# Sensor_Module_0x06_CO2_CCS811_v2.net
KiCad netlist of a schematic drawn in EAGLE
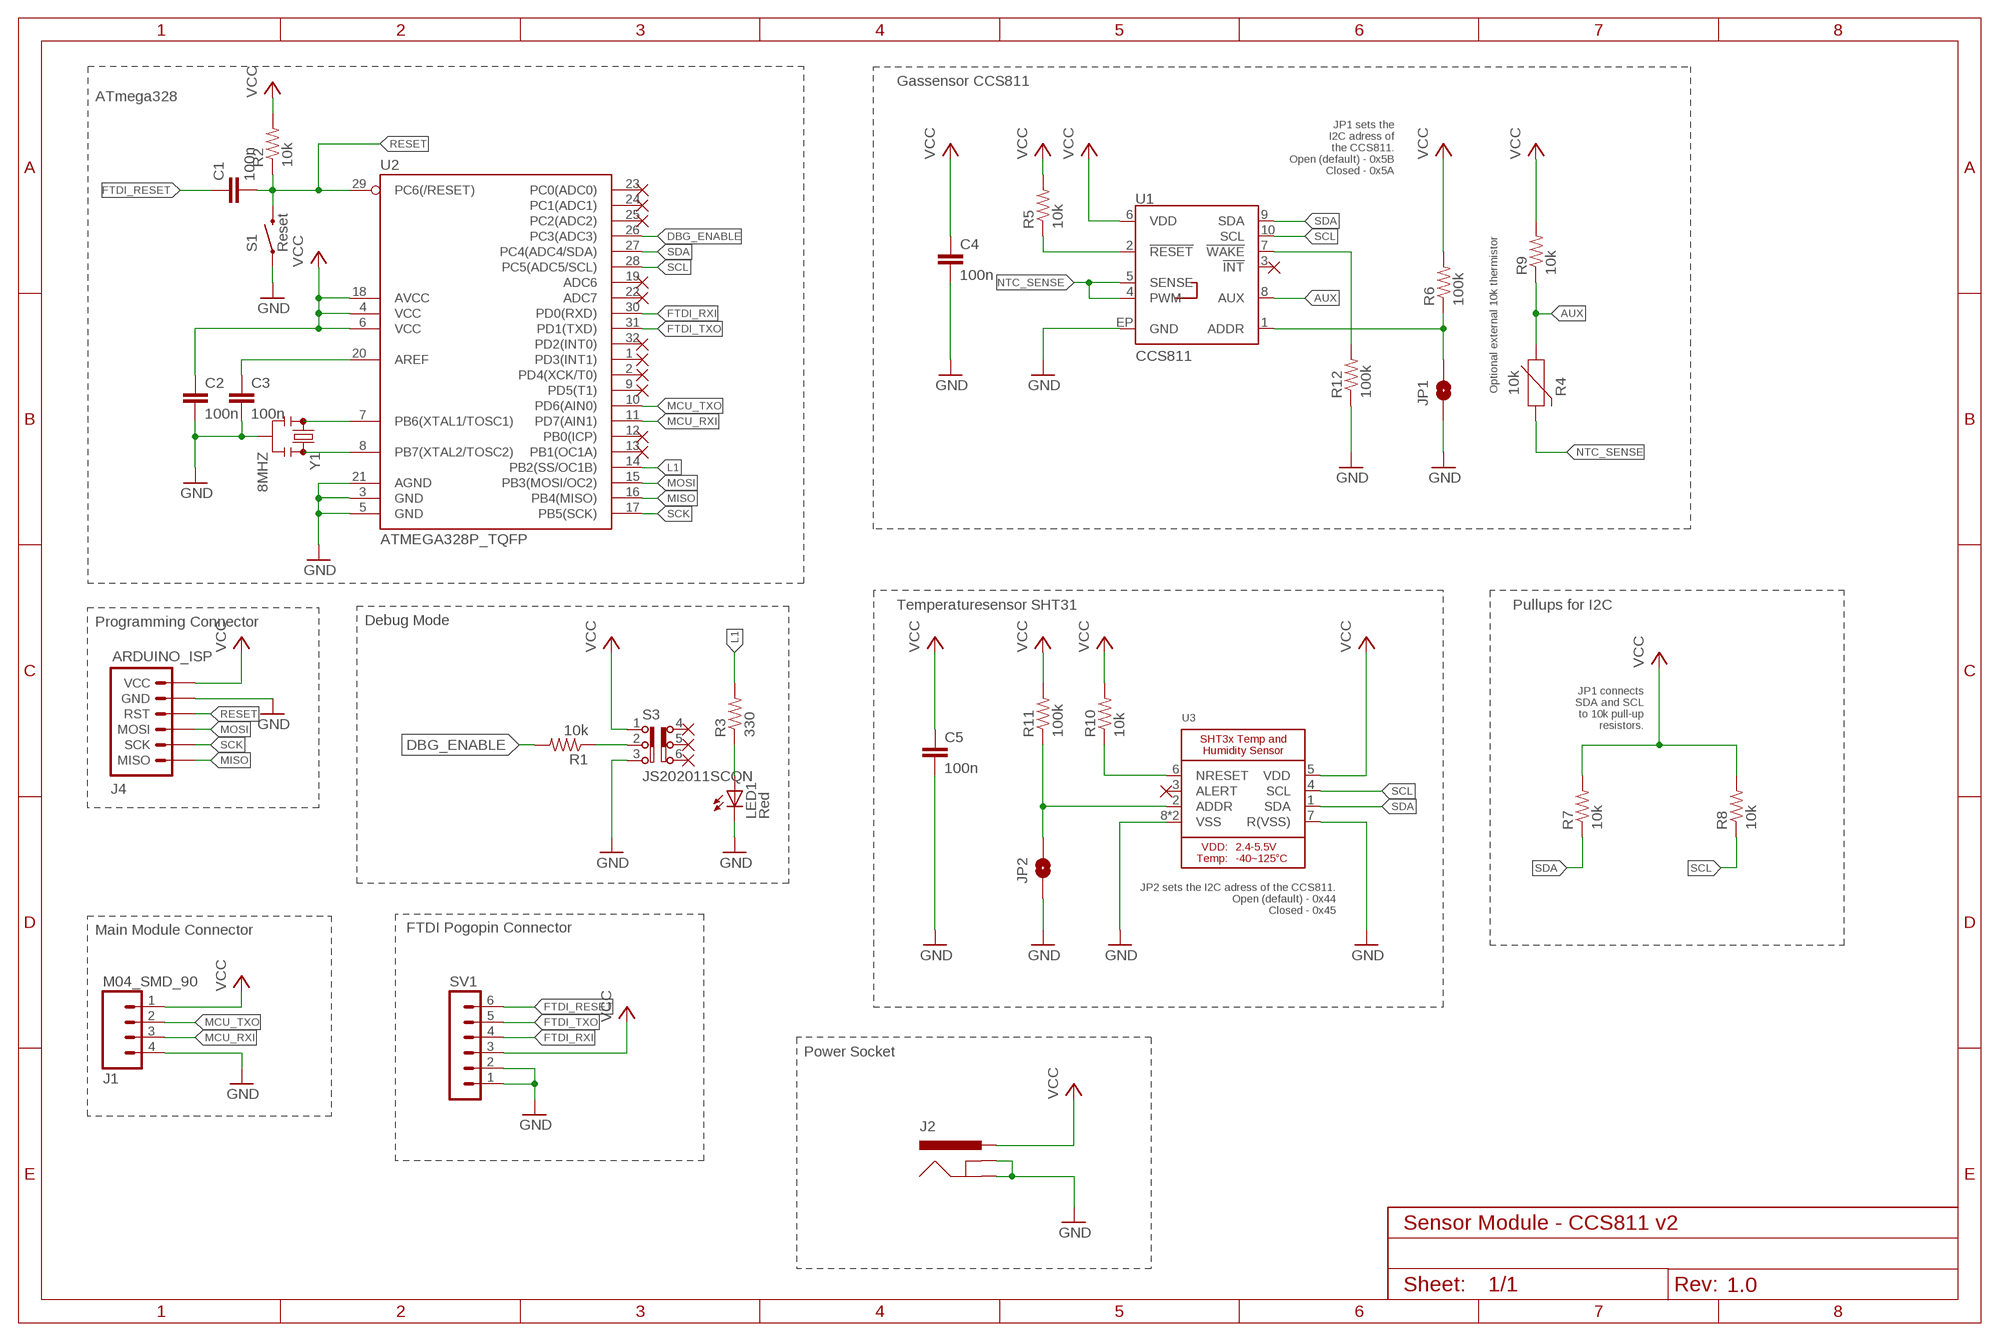
[diagram p0: schematic, sheet 1]

(export (version "E")
  (design (tool "Eeschema 10.0.6"))
  (components
    (comp (ref "C1")
      (value "100n")
      (footprint "eagle-import:C0805")
      (libsource (lib "eagle-import") (part "C"))
    )
    (comp (ref "C2")
      (value "100n")
      (footprint "eagle-import:C0805")
      (libsource (lib "eagle-import") (part "C"))
    )
    (comp (ref "C3")
      (value "100n")
      (footprint "eagle-import:C0805")
      (libsource (lib "eagle-import") (part "C"))
    )
    (comp (ref "C4")
      (value "100n")
      (footprint "eagle-import:C0805")
      (libsource (lib "eagle-import") (part "C"))
    )
    (comp (ref "C5")
      (value "100n")
      (footprint "eagle-import:C0805")
      (libsource (lib "eagle-import") (part "C"))
    )
    (comp (ref "J1")
      (value "M04_SMD_90")
      (footprint "eagle-import:M04_SMD_90")
      (libsource (lib "eagle-import") (part "M04_SMD_90"))
    )
    (comp (ref "J2")
      (value "5.5x2.1mm Barrel")
      (footprint "eagle-import:POWER_JACK_SMD")
      (libsource (lib "eagle-import") (part "POWER_JACKSMD"))
    )
    (comp (ref "J4")
      (value "ARDUINO_ISP")
      (footprint "eagle-import:M-2X3")
      (libsource (lib "eagle-import") (part "ARDUINO_ISP"))
    )
    (comp (ref "JP1")
      (value "SPARKFUN-JUMPERS_JUMPER-SMT_2_NO_SILK")
      (footprint "eagle-import:SPARKFUN-JUMPERS_SMT-JUMPER_2_NO_SILK")
      (libsource (lib "eagle-import") (part "SPARKFUN-JUMPERS_JUMPER-SMT_2_NO_SILK"))
    )
    (comp (ref "JP2")
      (value "SPARKFUN-JUMPERS_JUMPER-SMT_2_NO_SILK")
      (footprint "eagle-import:SPARKFUN-JUMPERS_SMT-JUMPER_2_NO_SILK")
      (libsource (lib "eagle-import") (part "SPARKFUN-JUMPERS_JUMPER-SMT_2_NO_SILK"))
    )
    (comp (ref "LED1")
      (value "Red")
      (footprint "eagle-import:SML0805")
      (libsource (lib "eagle-import") (part "LEDSML0805"))
    )
    (comp (ref "R1")
      (value "10k")
      (footprint "eagle-import:0805")
      (libsource (lib "eagle-import") (part "RESISTOR0805-RES"))
    )
    (comp (ref "R2")
      (value "10k")
      (footprint "eagle-import:0805")
      (libsource (lib "eagle-import") (part "RESISTOR0805-RES"))
    )
    (comp (ref "R3")
      (value "330")
      (footprint "eagle-import:0805")
      (libsource (lib "eagle-import") (part "RESISTOR0805-RES"))
    )
    (comp (ref "R4")
      (value "10k")
      (footprint "eagle-import:CCS811_BREAKOUT_TEMP_0603")
      (libsource (lib "eagle-import") (part "CCS811_BREAKOUT_TEMP_NTC-THERMISTOR-0603"))
    )
    (comp (ref "R5")
      (value "10k")
      (footprint "eagle-import:0805")
      (libsource (lib "eagle-import") (part "RESISTOR0805-RES"))
    )
    (comp (ref "R6")
      (value "100k")
      (footprint "eagle-import:0805")
      (libsource (lib "eagle-import") (part "RESISTOR0805-RES"))
    )
    (comp (ref "R7")
      (value "10k")
      (footprint "eagle-import:0805")
      (libsource (lib "eagle-import") (part "RESISTOR0805-RES"))
    )
    (comp (ref "R8")
      (value "10k")
      (footprint "eagle-import:0805")
      (libsource (lib "eagle-import") (part "RESISTOR0805-RES"))
    )
    (comp (ref "R9")
      (value "10k")
      (footprint "eagle-import:0805")
      (libsource (lib "eagle-import") (part "RESISTOR0805-RES"))
    )
    (comp (ref "R10")
      (value "10k")
      (footprint "eagle-import:0805")
      (libsource (lib "eagle-import") (part "RESISTOR0805-RES"))
    )
    (comp (ref "R11")
      (value "100k")
      (footprint "eagle-import:0805")
      (libsource (lib "eagle-import") (part "RESISTOR0805-RES"))
    )
    (comp (ref "R12")
      (value "100k")
      (footprint "eagle-import:0805")
      (libsource (lib "eagle-import") (part "RESISTOR0805-RES"))
    )
    (comp (ref "S1")
      (value "Reset")
      (footprint "eagle-import:M-PUSHBUTTON-SMD")
      (libsource (lib "eagle-import") (part "PUSHBUTTON"))
    )
    (comp (ref "S3")
      (value "JS202011SCQN")
      (footprint "eagle-import:JS202011SCQN")
      (libsource (lib "eagle-import") (part "JS202011SCQN"))
    )
    (comp (ref "SV1")
      (value "MA06-1")
      (footprint "eagle-import:MA06-1")
      (libsource (lib "eagle-import") (part "MA06-1"))
    )
    (comp (ref "U1")
      (value "CCS811")
      (footprint "eagle-import:CCS811_BREAKOUT_TEMP_LGA10")
      (libsource (lib "eagle-import") (part "CCS811_BREAKOUT_TEMP_CCS811"))
    )
    (comp (ref "U2")
      (value "ATMEGA328P_TQFP")
      (footprint "eagle-import:TQFP32-08")
      (libsource (lib "eagle-import") (part "ATMEGA328P_TQFP"))
    )
    (comp (ref "U3")
      (value "MICROBUILDER_SHT3X")
      (footprint "eagle-import:MICROBUILDER_SHT3X")
      (libsource (lib "eagle-import") (part "MICROBUILDER_SHT3X"))
    )
    (comp (ref "Y1")
      (value "8MHZ")
      (footprint "eagle-import:RESONATOR-SMD")
      (libsource (lib "eagle-import") (part "RESONATOR8MHZ"))
    )
  )
  (nets
    (net (code "1") (name "AUX") (class "Default")
      (node (ref "R4") (pin "1") (pinfunction "1_1") (pintype "bidirectional"))
      (node (ref "R9") (pin "1") (pinfunction "1_1") (pintype "passive"))
      (node (ref "U1") (pin "8") (pinfunction "AUX_8") (pintype "bidirectional"))
    )
    (net (code "2") (name "DBG_ENABLE") (class "Default")
      (node (ref "R1") (pin "2") (pinfunction "2_2") (pintype "passive"))
      (node (ref "U2") (pin "26") (pinfunction "PC3(ADC3)_26") (pintype "bidirectional"))
    )
    (net (code "3") (name "FTDI_RESET") (class "Default")
      (node (ref "C1") (pin "1") (pinfunction "1_1") (pintype "passive"))
      (node (ref "SV1") (pin "6") (pinfunction "6_6") (pintype "passive"))
    )
    (net (code "4") (name "FTDI_RXI") (class "Default")
      (node (ref "SV1") (pin "4") (pinfunction "4_4") (pintype "passive"))
      (node (ref "U2") (pin "30") (pinfunction "PD0(RXD)_30") (pintype "bidirectional"))
    )
    (net (code "5") (name "FTDI_TXO") (class "Default")
      (node (ref "SV1") (pin "5") (pinfunction "5_5") (pintype "passive"))
      (node (ref "U2") (pin "31") (pinfunction "PD1(TXD)_31") (pintype "bidirectional"))
    )
    (net (code "6") (name "GND") (class "Default")
      (node (ref "C2") (pin "2") (pinfunction "2_2") (pintype "passive"))
      (node (ref "C3") (pin "2") (pinfunction "2_2") (pintype "passive"))
      (node (ref "C4") (pin "2") (pinfunction "2_2") (pintype "passive"))
      (node (ref "C5") (pin "2") (pinfunction "2_2") (pintype "passive"))
      (node (ref "J1") (pin "4") (pinfunction "4_4") (pintype "passive"))
      (node (ref "J2") (pin "GND") (pinfunction "GNDBREAK_GND") (pintype "bidirectional"))
      (node (ref "J2") (pin "P$4") (pinfunction "GND_P$4") (pintype "bidirectional"))
      (node (ref "J4") (pin "P$5") (pinfunction "GND_P$5") (pintype "passive"))
      (node (ref "JP1") (pin "1") (pinfunction "1_1") (pintype "passive"))
      (node (ref "JP2") (pin "1") (pinfunction "1_1") (pintype "passive"))
      (node (ref "LED1") (pin "C") (pinfunction "C_C") (pintype "passive"))
      (node (ref "R12") (pin "1") (pinfunction "1_1") (pintype "passive"))
      (node (ref "S1") (pin "1") (pinfunction "LEFT_1") (pintype "passive"))
      (node (ref "S1") (pin "2") (pinfunction "LEFT_2") (pintype "passive"))
      (node (ref "S3") (pin "3") (pinfunction "3_3") (pintype "passive"))
      (node (ref "SV1") (pin "1") (pinfunction "1_1") (pintype "passive"))
      (node (ref "SV1") (pin "2") (pinfunction "2_2") (pintype "passive"))
      (node (ref "U1") (pin "EP") (pinfunction "GND_EP") (pintype "bidirectional"))
      (node (ref "U2") (pin "21") (pinfunction "AGND_21") (pintype "bidirectional"))
      (node (ref "U2") (pin "3") (pinfunction "GND_3") (pintype "bidirectional"))
      (node (ref "U2") (pin "5") (pinfunction "GND_5") (pintype "bidirectional"))
      (node (ref "U3") (pin "7") (pinfunction "R(VSS)_7") (pintype "bidirectional"))
      (node (ref "U3") (pin "8") (pinfunction "VSS_8") (pintype "power_in"))
      (node (ref "U3") (pin "THERMAL") (pinfunction "VSS_THERMAL") (pintype "power_in"))
      (node (ref "Y1") (pin "2") (pinfunction "2_2") (pintype "passive"))
    )
    (net (code "7") (name "L1") (class "Default")
      (node (ref "R3") (pin "2") (pinfunction "2_2") (pintype "passive"))
      (node (ref "U2") (pin "14") (pinfunction "PB2(SS/OC1B)_14") (pintype "bidirectional"))
    )
    (net (code "8") (name "MCU_RXI") (class "Default")
      (node (ref "J1") (pin "3") (pinfunction "3_3") (pintype "passive"))
      (node (ref "U2") (pin "11") (pinfunction "PD7(AIN1)_11") (pintype "bidirectional"))
    )
    (net (code "9") (name "MCU_TXO") (class "Default")
      (node (ref "J1") (pin "2") (pinfunction "2_2") (pintype "passive"))
      (node (ref "U2") (pin "10") (pinfunction "PD6(AIN0)_10") (pintype "bidirectional"))
    )
    (net (code "10") (name "MISO") (class "Default")
      (node (ref "J4") (pin "P$1") (pinfunction "MISO_P$1") (pintype "passive"))
      (node (ref "U2") (pin "16") (pinfunction "PB4(MISO)_16") (pintype "bidirectional"))
    )
    (net (code "11") (name "MOSI") (class "Default")
      (node (ref "J4") (pin "P$3") (pinfunction "MOSI_P$3") (pintype "passive"))
      (node (ref "U2") (pin "15") (pinfunction "PB3(MOSI/OC2)_15") (pintype "bidirectional"))
    )
    (net (code "12") (name "NTC_SENSE") (class "Default")
      (node (ref "R4") (pin "2") (pinfunction "2_2") (pintype "bidirectional"))
      (node (ref "U1") (pin "4") (pinfunction "PWM_4") (pintype "bidirectional"))
      (node (ref "U1") (pin "5") (pinfunction "SENSE_5") (pintype "bidirectional"))
    )
    (net (code "13") (name "Net-(LED1-PadA)") (class "Default")
      (node (ref "LED1") (pin "A") (pinfunction "A_A") (pintype "passive"))
      (node (ref "R3") (pin "1") (pinfunction "1_1") (pintype "passive"))
    )
    (net (code "14") (name "Net-(R1-Pad1)") (class "Default")
      (node (ref "R1") (pin "1") (pinfunction "1_1") (pintype "passive"))
      (node (ref "S3") (pin "2") (pinfunction "2_2") (pintype "passive"))
    )
    (net (code "15") (name "Net-(U1-ADDR)") (class "Default")
      (node (ref "JP1") (pin "2") (pinfunction "2_2") (pintype "passive"))
      (node (ref "R6") (pin "1") (pinfunction "1_1") (pintype "passive"))
      (node (ref "U1") (pin "1") (pinfunction "ADDR_1") (pintype "bidirectional"))
    )
    (net (code "16") (name "Net-(U1-~{RESET})") (class "Default")
      (node (ref "R5") (pin "1") (pinfunction "1_1") (pintype "passive"))
      (node (ref "U1") (pin "2") (pinfunction "~{RESET}_2") (pintype "bidirectional"))
    )
    (net (code "17") (name "Net-(U1-~{WAKE})") (class "Default")
      (node (ref "R12") (pin "2") (pinfunction "2_2") (pintype "passive"))
      (node (ref "U1") (pin "7") (pinfunction "~{WAKE}_7") (pintype "bidirectional"))
    )
    (net (code "18") (name "Net-(U2-AREF)") (class "Default")
      (node (ref "C3") (pin "1") (pinfunction "1_1") (pintype "passive"))
      (node (ref "U2") (pin "20") (pinfunction "AREF_20") (pintype "bidirectional"))
    )
    (net (code "19") (name "Net-(U2-PB6(XTAL1{slash}TOSC1))") (class "Default")
      (node (ref "U2") (pin "7") (pinfunction "PB6(XTAL1/TOSC1)_7") (pintype "bidirectional"))
      (node (ref "Y1") (pin "1") (pinfunction "1_1") (pintype "passive"))
    )
    (net (code "20") (name "Net-(U2-PB7(XTAL2{slash}TOSC2))") (class "Default")
      (node (ref "U2") (pin "8") (pinfunction "PB7(XTAL2/TOSC2)_8") (pintype "bidirectional"))
      (node (ref "Y1") (pin "3") (pinfunction "3_3") (pintype "passive"))
    )
    (net (code "21") (name "Net-(U3-ADDR)") (class "Default")
      (node (ref "JP2") (pin "2") (pinfunction "2_2") (pintype "passive"))
      (node (ref "R11") (pin "1") (pinfunction "1_1") (pintype "passive"))
      (node (ref "U3") (pin "2") (pinfunction "ADDR_2") (pintype "bidirectional"))
    )
    (net (code "22") (name "Net-(U3-NRESET)") (class "Default")
      (node (ref "R10") (pin "1") (pinfunction "1_1") (pintype "passive"))
      (node (ref "U3") (pin "6") (pinfunction "NRESET_6") (pintype "bidirectional"))
    )
    (net (code "23") (name "RESET") (class "Default")
      (node (ref "C1") (pin "2") (pinfunction "2_2") (pintype "passive"))
      (node (ref "J4") (pin "P$4") (pinfunction "RST_P$4") (pintype "passive"))
      (node (ref "R2") (pin "1") (pinfunction "1_1") (pintype "passive"))
      (node (ref "S1") (pin "3") (pinfunction "RIGHT_3") (pintype "passive"))
      (node (ref "S1") (pin "4") (pinfunction "RIGHT_4") (pintype "passive"))
      (node (ref "U2") (pin "29") (pinfunction "PC6(/RESET)_29") (pintype "bidirectional"))
    )
    (net (code "24") (name "SCK") (class "Default")
      (node (ref "J4") (pin "P$2") (pinfunction "SCK_P$2") (pintype "passive"))
      (node (ref "U2") (pin "17") (pinfunction "PB5(SCK)_17") (pintype "bidirectional"))
    )
    (net (code "25") (name "SCL") (class "Default")
      (node (ref "R8") (pin "1") (pinfunction "1_1") (pintype "passive"))
      (node (ref "U1") (pin "10") (pinfunction "SCL_10") (pintype "bidirectional"))
      (node (ref "U2") (pin "28") (pinfunction "PC5(ADC5/SCL)_28") (pintype "bidirectional"))
      (node (ref "U3") (pin "4") (pinfunction "SCL_4") (pintype "bidirectional"))
    )
    (net (code "26") (name "SDA") (class "Default")
      (node (ref "R7") (pin "1") (pinfunction "1_1") (pintype "passive"))
      (node (ref "U1") (pin "9") (pinfunction "SDA_9") (pintype "bidirectional"))
      (node (ref "U2") (pin "27") (pinfunction "PC4(ADC4/SDA)_27") (pintype "bidirectional"))
      (node (ref "U3") (pin "1") (pinfunction "SDA_1") (pintype "bidirectional"))
    )
    (net (code "27") (name "VCC") (class "Default")
      (node (ref "C2") (pin "1") (pinfunction "1_1") (pintype "passive"))
      (node (ref "C4") (pin "1") (pinfunction "1_1") (pintype "passive"))
      (node (ref "C5") (pin "1") (pinfunction "1_1") (pintype "passive"))
      (node (ref "J1") (pin "1") (pinfunction "1_1") (pintype "passive"))
      (node (ref "J2") (pin "VIN0") (pinfunction "PWR_VIN0") (pintype "bidirectional"))
      (node (ref "J2") (pin "VIN1") (pinfunction "PWR_VIN1") (pintype "bidirectional"))
      (node (ref "J4") (pin "P$6") (pinfunction "VCC_P$6") (pintype "passive"))
      (node (ref "R10") (pin "2") (pinfunction "2_2") (pintype "passive"))
      (node (ref "R11") (pin "2") (pinfunction "2_2") (pintype "passive"))
      (node (ref "R2") (pin "2") (pinfunction "2_2") (pintype "passive"))
      (node (ref "R5") (pin "2") (pinfunction "2_2") (pintype "passive"))
      (node (ref "R6") (pin "2") (pinfunction "2_2") (pintype "passive"))
      (node (ref "R7") (pin "2") (pinfunction "2_2") (pintype "passive"))
      (node (ref "R8") (pin "2") (pinfunction "2_2") (pintype "passive"))
      (node (ref "R9") (pin "2") (pinfunction "2_2") (pintype "passive"))
      (node (ref "S3") (pin "1") (pinfunction "1_1") (pintype "passive"))
      (node (ref "SV1") (pin "3") (pinfunction "3_3") (pintype "passive"))
      (node (ref "U1") (pin "6") (pinfunction "VDD_6") (pintype "bidirectional"))
      (node (ref "U2") (pin "18") (pinfunction "AVCC_18") (pintype "bidirectional"))
      (node (ref "U2") (pin "4") (pinfunction "VCC_4") (pintype "bidirectional"))
      (node (ref "U2") (pin "6") (pinfunction "VCC_6") (pintype "bidirectional"))
      (node (ref "U3") (pin "5") (pinfunction "VDD_5") (pintype "power_in"))
    )
    (net (code "28") (name "unconnected-(S3-Pad4)") (class "Default")
      (node (ref "S3") (pin "4") (pinfunction "4_4") (pintype "passive"))
    )
    (net (code "29") (name "unconnected-(S3-Pad5)") (class "Default")
      (node (ref "S3") (pin "5") (pinfunction "5_5") (pintype "passive"))
    )
    (net (code "30") (name "unconnected-(S3-Pad6)") (class "Default")
      (node (ref "S3") (pin "6") (pinfunction "6_6") (pintype "passive"))
    )
    (net (code "31") (name "unconnected-(U1-~{INT}-Pad3)") (class "Default")
      (node (ref "U1") (pin "3") (pinfunction "~{INT}_3") (pintype "bidirectional"))
    )
    (net (code "32") (name "unconnected-(U2-ADC6-Pad19)") (class "Default")
      (node (ref "U2") (pin "19") (pinfunction "ADC6_19") (pintype "bidirectional"))
    )
    (net (code "33") (name "unconnected-(U2-ADC7-Pad22)") (class "Default")
      (node (ref "U2") (pin "22") (pinfunction "ADC7_22") (pintype "bidirectional"))
    )
    (net (code "34") (name "unconnected-(U2-PB0(ICP)-Pad12)") (class "Default")
      (node (ref "U2") (pin "12") (pinfunction "PB0(ICP)_12") (pintype "bidirectional"))
    )
    (net (code "35") (name "unconnected-(U2-PB1(OC1A)-Pad13)") (class "Default")
      (node (ref "U2") (pin "13") (pinfunction "PB1(OC1A)_13") (pintype "bidirectional"))
    )
    (net (code "36") (name "unconnected-(U2-PC0(ADC0)-Pad23)") (class "Default")
      (node (ref "U2") (pin "23") (pinfunction "PC0(ADC0)_23") (pintype "bidirectional"))
    )
    (net (code "37") (name "unconnected-(U2-PC1(ADC1)-Pad24)") (class "Default")
      (node (ref "U2") (pin "24") (pinfunction "PC1(ADC1)_24") (pintype "bidirectional"))
    )
    (net (code "38") (name "unconnected-(U2-PC2(ADC2)-Pad25)") (class "Default")
      (node (ref "U2") (pin "25") (pinfunction "PC2(ADC2)_25") (pintype "bidirectional"))
    )
    (net (code "39") (name "unconnected-(U2-PD2(INT0)-Pad32)") (class "Default")
      (node (ref "U2") (pin "32") (pinfunction "PD2(INT0)_32") (pintype "bidirectional"))
    )
    (net (code "40") (name "unconnected-(U2-PD3(INT1)-Pad1)") (class "Default")
      (node (ref "U2") (pin "1") (pinfunction "PD3(INT1)_1") (pintype "bidirectional"))
    )
    (net (code "41") (name "unconnected-(U2-PD4(XCK{slash}T0)-Pad2)") (class "Default")
      (node (ref "U2") (pin "2") (pinfunction "PD4(XCK/T0)_2") (pintype "bidirectional"))
    )
    (net (code "42") (name "unconnected-(U2-PD5(T1)-Pad9)") (class "Default")
      (node (ref "U2") (pin "9") (pinfunction "PD5(T1)_9") (pintype "bidirectional"))
    )
    (net (code "43") (name "unconnected-(U3-ALERT-Pad3)") (class "Default")
      (node (ref "U3") (pin "3") (pinfunction "ALERT_3") (pintype "bidirectional"))
    )
  )
)
